# M212X.net
KiCad netlist of a schematic drawn in EAGLE
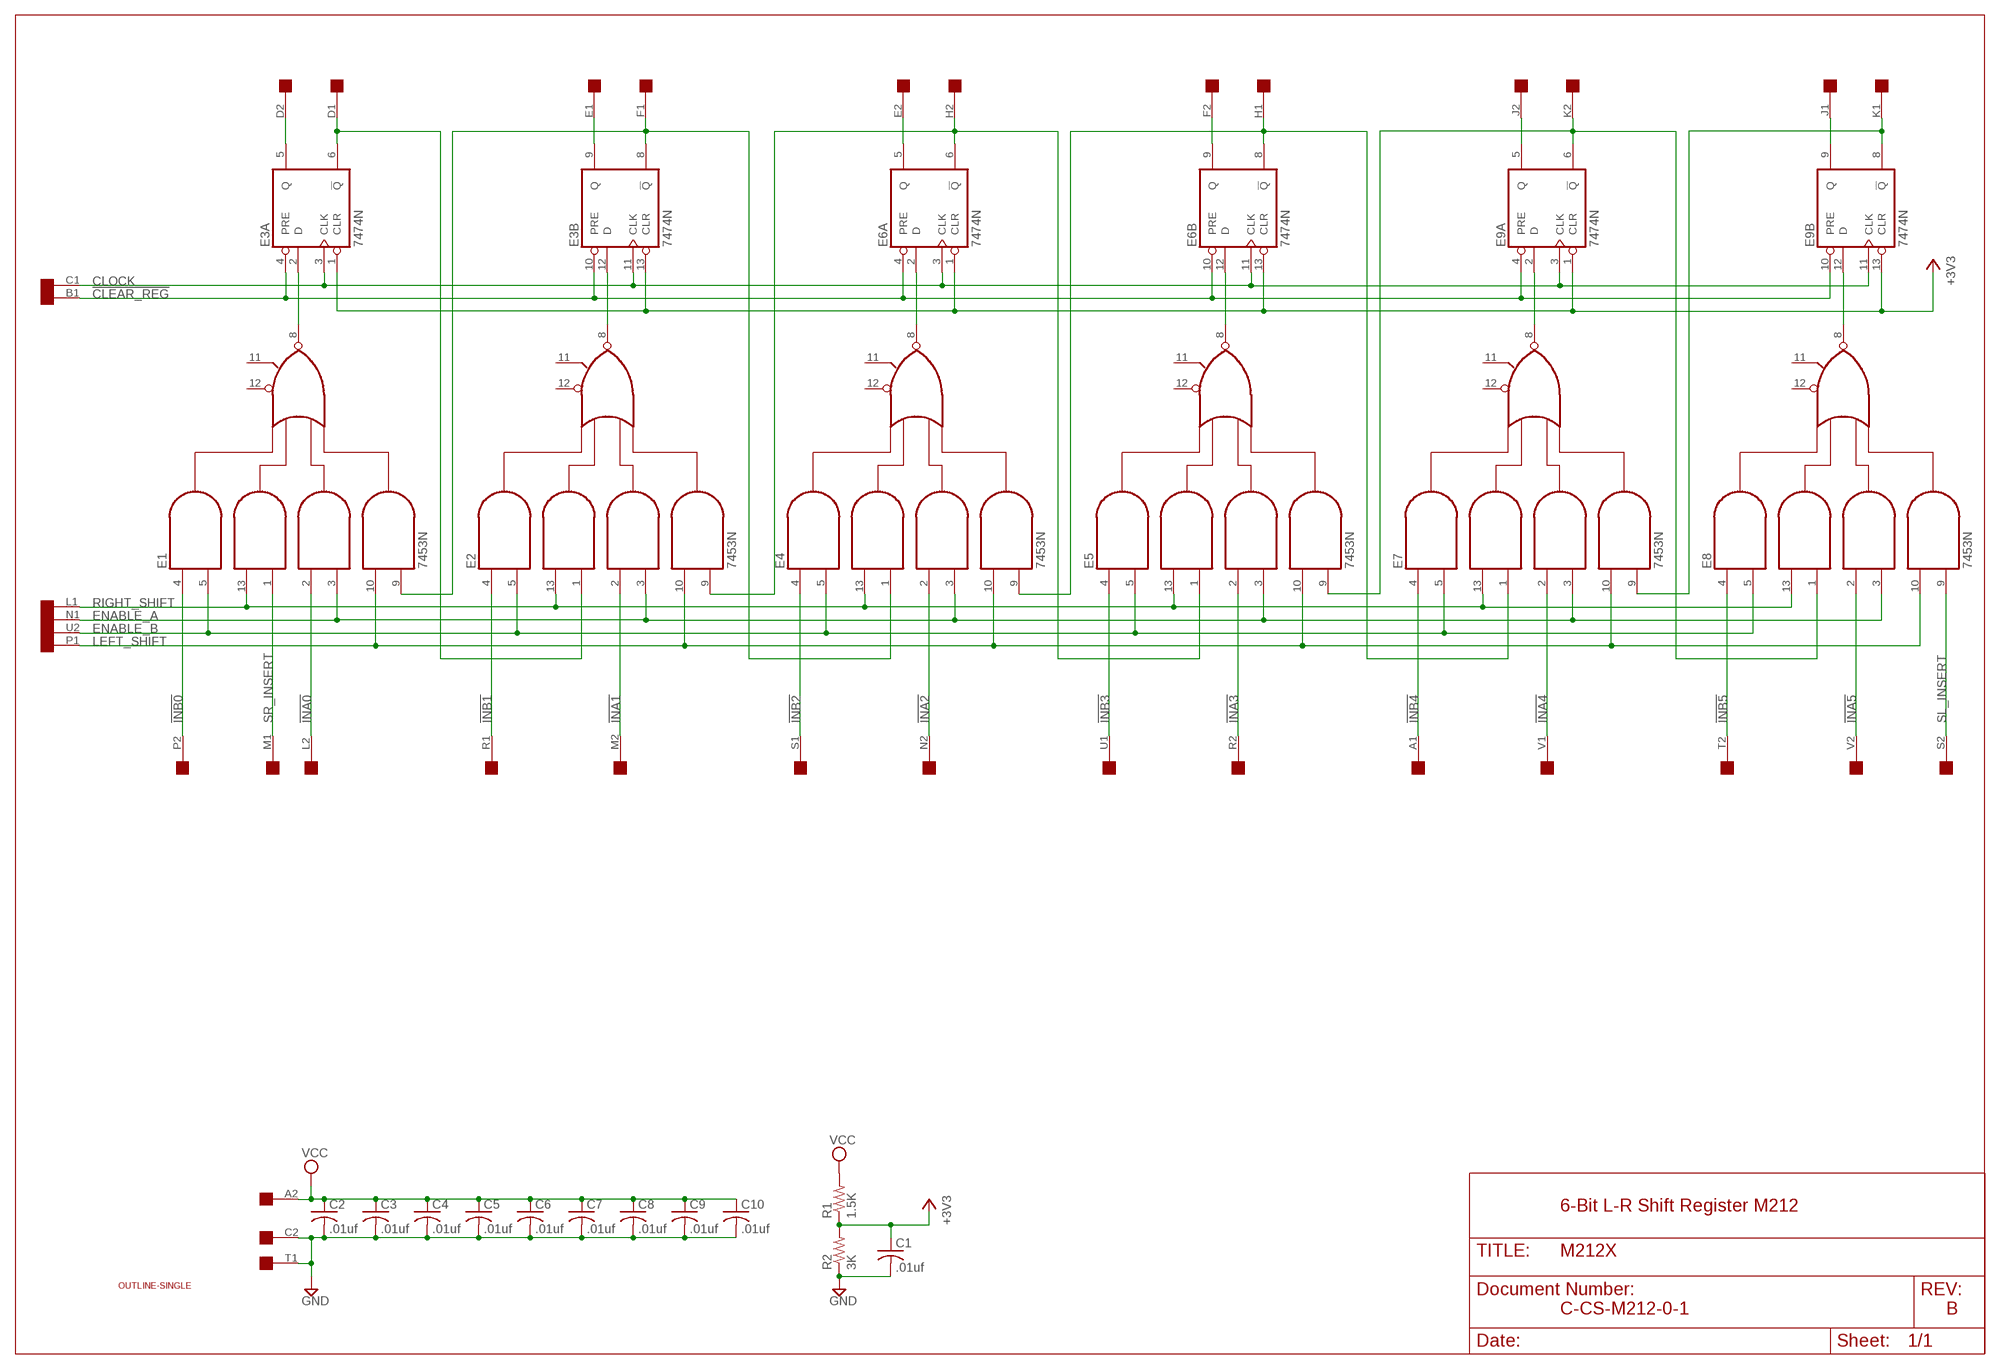
[diagram p0: schematic, sheet 1]

(export (version "E")
  (design (tool "Eeschema 10.0.6"))
  (components
    (comp (ref "C1")
      (value ".01uf")
      (footprint "eagle-import:C050-025X075")
      (libsource (lib "eagle-import") (part "C-US050-025X075"))
    )
    (comp (ref "C2")
      (value ".01uf")
      (footprint "eagle-import:C075-032X103")
      (libsource (lib "eagle-import") (part "C-US075-032X103"))
    )
    (comp (ref "C3")
      (value ".01uf")
      (footprint "eagle-import:C075-032X103")
      (libsource (lib "eagle-import") (part "C-US075-032X103"))
    )
    (comp (ref "C4")
      (value ".01uf")
      (footprint "eagle-import:C075-032X103")
      (libsource (lib "eagle-import") (part "C-US075-032X103"))
    )
    (comp (ref "C5")
      (value ".01uf")
      (footprint "eagle-import:C075-032X103")
      (libsource (lib "eagle-import") (part "C-US075-032X103"))
    )
    (comp (ref "C6")
      (value ".01uf")
      (footprint "eagle-import:C075-032X103")
      (libsource (lib "eagle-import") (part "C-US075-032X103"))
    )
    (comp (ref "C7")
      (value ".01uf")
      (footprint "eagle-import:C075-032X103")
      (libsource (lib "eagle-import") (part "C-US075-032X103"))
    )
    (comp (ref "C8")
      (value ".01uf")
      (footprint "eagle-import:C075-032X103")
      (libsource (lib "eagle-import") (part "C-US075-032X103"))
    )
    (comp (ref "C9")
      (value ".01uf")
      (footprint "eagle-import:C075-032X103")
      (libsource (lib "eagle-import") (part "C-US075-032X103"))
    )
    (comp (ref "C10")
      (value ".01uf")
      (footprint "eagle-import:C075-032X103")
      (libsource (lib "eagle-import") (part "C-US075-032X103"))
    )
    (comp (ref "E1")
      (value "7453N")
      (footprint "eagle-import:DIL14")
      (libsource (lib "eagle-import") (part "7453N"))
    )
    (comp (ref "E2")
      (value "7453N")
      (footprint "eagle-import:DIL14")
      (libsource (lib "eagle-import") (part "7453N"))
    )
    (comp (ref "E3")
      (value "7474N")
      (footprint "eagle-import:DIL14")
      (libsource (lib "eagle-import") (part "7474NS"))
    )
    (comp (ref "E4")
      (value "7453N")
      (footprint "eagle-import:DIL14")
      (libsource (lib "eagle-import") (part "7453N"))
    )
    (comp (ref "E5")
      (value "7453N")
      (footprint "eagle-import:DIL14")
      (libsource (lib "eagle-import") (part "7453N"))
    )
    (comp (ref "E6")
      (value "7474N")
      (footprint "eagle-import:DIL14")
      (libsource (lib "eagle-import") (part "7474NS"))
    )
    (comp (ref "E7")
      (value "7453N")
      (footprint "eagle-import:DIL14")
      (libsource (lib "eagle-import") (part "7453N"))
    )
    (comp (ref "E8")
      (value "7453N")
      (footprint "eagle-import:DIL14")
      (libsource (lib "eagle-import") (part "7453N"))
    )
    (comp (ref "E9")
      (value "7474N")
      (footprint "eagle-import:DIL14")
      (libsource (lib "eagle-import") (part "7474NS"))
    )
    (comp (ref "EDGE1")
      (value "EDGE-2CONNECTOR")
      (footprint "eagle-import:EDGE-CON2")
      (libsource (lib "eagle-import") (part "EDGE-2CONNECTOR"))
    )
    (comp (ref "R1")
      (value "1.5K")
      (footprint "eagle-import:0207_10")
      (libsource (lib "eagle-import") (part "R-US_0207/10"))
    )
    (comp (ref "R2")
      (value "3K")
      (footprint "eagle-import:0207_10")
      (libsource (lib "eagle-import") (part "R-US_0207/10"))
    )
    (comp (ref "U$1")
      (value "OUTLINE-SINGLE")
      (footprint "eagle-import:SINGLE")
      (libsource (lib "eagle-import") (part "OUTLINE-SINGLE"))
    )
  )
  (nets
    (net (code "1") (name "+3V3") (class "Default")
      (node (ref "C1") (pin "1") (pinfunction "1_1") (pintype "passive"))
      (node (ref "E3") (pin "1") (pinfunction "CLR_1") (pintype "input"))
      (node (ref "E3") (pin "13") (pinfunction "CLR_13") (pintype "input"))
      (node (ref "E6") (pin "1") (pinfunction "CLR_1") (pintype "input"))
      (node (ref "E6") (pin "13") (pinfunction "CLR_13") (pintype "input"))
      (node (ref "E9") (pin "1") (pinfunction "CLR_1") (pintype "input"))
      (node (ref "E9") (pin "13") (pinfunction "CLR_13") (pintype "input"))
      (node (ref "R1") (pin "1") (pinfunction "1_1") (pintype "passive"))
      (node (ref "R2") (pin "2") (pinfunction "2_2") (pintype "passive"))
    )
    (net (code "2") (name "/CLOCK") (class "Default")
      (node (ref "E3") (pin "11") (pinfunction "CLK_11") (pintype "input"))
      (node (ref "E3") (pin "3") (pinfunction "CLK_3") (pintype "input"))
      (node (ref "E6") (pin "11") (pinfunction "CLK_11") (pintype "input"))
      (node (ref "E6") (pin "3") (pinfunction "CLK_3") (pintype "input"))
      (node (ref "E9") (pin "11") (pinfunction "CLK_11") (pintype "input"))
      (node (ref "E9") (pin "3") (pinfunction "CLK_3") (pintype "input"))
      (node (ref "EDGE1") (pin "C1") (pinfunction "1_C1") (pintype "bidirectional"))
    )
    (net (code "3") (name "/ENABLE_A") (class "Default")
      (node (ref "E1") (pin "3") (pinfunction "I6_3") (pintype "input"))
      (node (ref "E2") (pin "3") (pinfunction "I6_3") (pintype "input"))
      (node (ref "E4") (pin "3") (pinfunction "I6_3") (pintype "input"))
      (node (ref "E5") (pin "3") (pinfunction "I6_3") (pintype "input"))
      (node (ref "E7") (pin "3") (pinfunction "I6_3") (pintype "input"))
      (node (ref "E8") (pin "3") (pinfunction "I6_3") (pintype "input"))
      (node (ref "EDGE1") (pin "N1") (pinfunction "1_N1") (pintype "bidirectional"))
    )
    (net (code "4") (name "/ENABLE_B") (class "Default")
      (node (ref "E1") (pin "5") (pinfunction "I2_5") (pintype "input"))
      (node (ref "E2") (pin "5") (pinfunction "I2_5") (pintype "input"))
      (node (ref "E4") (pin "5") (pinfunction "I2_5") (pintype "input"))
      (node (ref "E5") (pin "5") (pinfunction "I2_5") (pintype "input"))
      (node (ref "E7") (pin "5") (pinfunction "I2_5") (pintype "input"))
      (node (ref "E8") (pin "5") (pinfunction "I2_5") (pintype "input"))
      (node (ref "EDGE1") (pin "U2") (pinfunction "1_U2") (pintype "bidirectional"))
    )
    (net (code "5") (name "/LEFT_SHIFT") (class "Default")
      (node (ref "E1") (pin "10") (pinfunction "I7_10") (pintype "input"))
      (node (ref "E2") (pin "10") (pinfunction "I7_10") (pintype "input"))
      (node (ref "E4") (pin "10") (pinfunction "I7_10") (pintype "input"))
      (node (ref "E5") (pin "10") (pinfunction "I7_10") (pintype "input"))
      (node (ref "E7") (pin "10") (pinfunction "I7_10") (pintype "input"))
      (node (ref "E8") (pin "10") (pinfunction "I7_10") (pintype "input"))
      (node (ref "EDGE1") (pin "P1") (pinfunction "1_P1") (pintype "bidirectional"))
    )
    (net (code "6") (name "/RIGHT_SHIFT") (class "Default")
      (node (ref "E1") (pin "13") (pinfunction "I3_13") (pintype "input"))
      (node (ref "E2") (pin "13") (pinfunction "I3_13") (pintype "input"))
      (node (ref "E4") (pin "13") (pinfunction "I3_13") (pintype "input"))
      (node (ref "E5") (pin "13") (pinfunction "I3_13") (pintype "input"))
      (node (ref "E7") (pin "13") (pinfunction "I3_13") (pintype "input"))
      (node (ref "E8") (pin "13") (pinfunction "I3_13") (pintype "input"))
      (node (ref "EDGE1") (pin "L1") (pinfunction "1_L1") (pintype "bidirectional"))
    )
    (net (code "7") (name "/SL_INSERT") (class "Default")
      (node (ref "E8") (pin "9") (pinfunction "I8_9") (pintype "input"))
      (node (ref "EDGE1") (pin "S2") (pinfunction "1_S2") (pintype "bidirectional"))
    )
    (net (code "8") (name "/SR_INSERT") (class "Default")
      (node (ref "E1") (pin "1") (pinfunction "I4_1") (pintype "input"))
      (node (ref "EDGE1") (pin "M1") (pinfunction "1_M1") (pintype "bidirectional"))
    )
    (net (code "9") (name "/~{CLEAR_REG}") (class "Default")
      (node (ref "E3") (pin "10") (pinfunction "PRE_10") (pintype "input"))
      (node (ref "E3") (pin "4") (pinfunction "PRE_4") (pintype "input"))
      (node (ref "E6") (pin "10") (pinfunction "PRE_10") (pintype "input"))
      (node (ref "E6") (pin "4") (pinfunction "PRE_4") (pintype "input"))
      (node (ref "E9") (pin "10") (pinfunction "PRE_10") (pintype "input"))
      (node (ref "E9") (pin "4") (pinfunction "PRE_4") (pintype "input"))
      (node (ref "EDGE1") (pin "B1") (pinfunction "1_B1") (pintype "bidirectional"))
    )
    (net (code "10") (name "/~{INA0}") (class "Default")
      (node (ref "E1") (pin "2") (pinfunction "I5_2") (pintype "input"))
      (node (ref "EDGE1") (pin "L2") (pinfunction "1_L2") (pintype "bidirectional"))
    )
    (net (code "11") (name "/~{INA1}") (class "Default")
      (node (ref "E2") (pin "2") (pinfunction "I5_2") (pintype "input"))
      (node (ref "EDGE1") (pin "M2") (pinfunction "1_M2") (pintype "bidirectional"))
    )
    (net (code "12") (name "/~{INA2}") (class "Default")
      (node (ref "E4") (pin "2") (pinfunction "I5_2") (pintype "input"))
      (node (ref "EDGE1") (pin "N2") (pinfunction "1_N2") (pintype "bidirectional"))
    )
    (net (code "13") (name "/~{INA3}") (class "Default")
      (node (ref "E5") (pin "2") (pinfunction "I5_2") (pintype "input"))
      (node (ref "EDGE1") (pin "R2") (pinfunction "1_R2") (pintype "bidirectional"))
    )
    (net (code "14") (name "/~{INA4}") (class "Default")
      (node (ref "E7") (pin "2") (pinfunction "I5_2") (pintype "input"))
      (node (ref "EDGE1") (pin "V1") (pinfunction "1_V1") (pintype "bidirectional"))
    )
    (net (code "15") (name "/~{INA5}") (class "Default")
      (node (ref "E8") (pin "2") (pinfunction "I5_2") (pintype "input"))
      (node (ref "EDGE1") (pin "V2") (pinfunction "1_V2") (pintype "bidirectional"))
    )
    (net (code "16") (name "/~{INB0}") (class "Default")
      (node (ref "E1") (pin "4") (pinfunction "I1_4") (pintype "input"))
      (node (ref "EDGE1") (pin "P2") (pinfunction "1_P2") (pintype "bidirectional"))
    )
    (net (code "17") (name "/~{INB1}") (class "Default")
      (node (ref "E2") (pin "4") (pinfunction "I1_4") (pintype "input"))
      (node (ref "EDGE1") (pin "R1") (pinfunction "1_R1") (pintype "bidirectional"))
    )
    (net (code "18") (name "/~{INB2}") (class "Default")
      (node (ref "E4") (pin "4") (pinfunction "I1_4") (pintype "input"))
      (node (ref "EDGE1") (pin "S1") (pinfunction "1_S1") (pintype "bidirectional"))
    )
    (net (code "19") (name "/~{INB3}") (class "Default")
      (node (ref "E5") (pin "4") (pinfunction "I1_4") (pintype "input"))
      (node (ref "EDGE1") (pin "U1") (pinfunction "1_U1") (pintype "bidirectional"))
    )
    (net (code "20") (name "/~{INB4}") (class "Default")
      (node (ref "E7") (pin "4") (pinfunction "I1_4") (pintype "input"))
      (node (ref "EDGE1") (pin "A1") (pinfunction "1_A1") (pintype "bidirectional"))
    )
    (net (code "21") (name "/~{INB5}") (class "Default")
      (node (ref "E8") (pin "4") (pinfunction "I1_4") (pintype "input"))
      (node (ref "EDGE1") (pin "T2") (pinfunction "1_T2") (pintype "bidirectional"))
    )
    (net (code "22") (name "GND") (class "Default")
      (node (ref "C1") (pin "2") (pinfunction "2_2") (pintype "passive"))
      (node (ref "C10") (pin "2") (pinfunction "2_2") (pintype "passive"))
      (node (ref "C2") (pin "2") (pinfunction "2_2") (pintype "passive"))
      (node (ref "C3") (pin "2") (pinfunction "2_2") (pintype "passive"))
      (node (ref "C4") (pin "2") (pinfunction "2_2") (pintype "passive"))
      (node (ref "C5") (pin "2") (pinfunction "2_2") (pintype "passive"))
      (node (ref "C6") (pin "2") (pinfunction "2_2") (pintype "passive"))
      (node (ref "C7") (pin "2") (pinfunction "2_2") (pintype "passive"))
      (node (ref "C8") (pin "2") (pinfunction "2_2") (pintype "passive"))
      (node (ref "C9") (pin "2") (pinfunction "2_2") (pintype "passive"))
      (node (ref "EDGE1") (pin "C2") (pinfunction "1_C2") (pintype "bidirectional"))
      (node (ref "EDGE1") (pin "T1") (pinfunction "1_T1") (pintype "bidirectional"))
      (node (ref "R2") (pin "1") (pinfunction "1_1") (pintype "passive"))
    )
    (net (code "23") (name "Net-(E1A-I8)") (class "Default")
      (node (ref "E1") (pin "9") (pinfunction "I8_9") (pintype "input"))
      (node (ref "E3") (pin "8") (pinfunction "~{Q}_8") (pintype "output"))
      (node (ref "E4") (pin "1") (pinfunction "I4_1") (pintype "input"))
      (node (ref "EDGE1") (pin "F1") (pinfunction "1_F1") (pintype "bidirectional"))
    )
    (net (code "24") (name "Net-(E1A-O)") (class "Default")
      (node (ref "E1") (pin "8") (pinfunction "O_8") (pintype "output"))
      (node (ref "E3") (pin "2") (pinfunction "D_2") (pintype "input"))
    )
    (net (code "25") (name "Net-(E2A-I4)") (class "Default")
      (node (ref "E2") (pin "1") (pinfunction "I4_1") (pintype "input"))
      (node (ref "E3") (pin "6") (pinfunction "~{Q}_6") (pintype "output"))
      (node (ref "EDGE1") (pin "D1") (pinfunction "1_D1") (pintype "bidirectional"))
    )
    (net (code "26") (name "Net-(E2A-I8)") (class "Default")
      (node (ref "E2") (pin "9") (pinfunction "I8_9") (pintype "input"))
      (node (ref "E5") (pin "1") (pinfunction "I4_1") (pintype "input"))
      (node (ref "E6") (pin "6") (pinfunction "~{Q}_6") (pintype "output"))
      (node (ref "EDGE1") (pin "H2") (pinfunction "1_H2") (pintype "bidirectional"))
    )
    (net (code "27") (name "Net-(E2A-O)") (class "Default")
      (node (ref "E2") (pin "8") (pinfunction "O_8") (pintype "output"))
      (node (ref "E3") (pin "12") (pinfunction "D_12") (pintype "input"))
    )
    (net (code "28") (name "Net-(E3A-Q)") (class "Default")
      (node (ref "E3") (pin "5") (pinfunction "Q_5") (pintype "output"))
      (node (ref "EDGE1") (pin "D2") (pinfunction "1_D2") (pintype "bidirectional"))
    )
    (net (code "29") (name "Net-(E3B-Q)") (class "Default")
      (node (ref "E3") (pin "9") (pinfunction "Q_9") (pintype "output"))
      (node (ref "EDGE1") (pin "E1") (pinfunction "1_E1") (pintype "bidirectional"))
    )
    (net (code "30") (name "Net-(E4A-I8)") (class "Default")
      (node (ref "E4") (pin "9") (pinfunction "I8_9") (pintype "input"))
      (node (ref "E6") (pin "8") (pinfunction "~{Q}_8") (pintype "output"))
      (node (ref "E7") (pin "1") (pinfunction "I4_1") (pintype "input"))
      (node (ref "EDGE1") (pin "H1") (pinfunction "1_H1") (pintype "bidirectional"))
    )
    (net (code "31") (name "Net-(E4A-O)") (class "Default")
      (node (ref "E4") (pin "8") (pinfunction "O_8") (pintype "output"))
      (node (ref "E6") (pin "2") (pinfunction "D_2") (pintype "input"))
    )
    (net (code "32") (name "Net-(E5A-I8)") (class "Default")
      (node (ref "E5") (pin "9") (pinfunction "I8_9") (pintype "input"))
      (node (ref "E8") (pin "1") (pinfunction "I4_1") (pintype "input"))
      (node (ref "E9") (pin "6") (pinfunction "~{Q}_6") (pintype "output"))
      (node (ref "EDGE1") (pin "K2") (pinfunction "1_K2") (pintype "bidirectional"))
    )
    (net (code "33") (name "Net-(E5A-O)") (class "Default")
      (node (ref "E5") (pin "8") (pinfunction "O_8") (pintype "output"))
      (node (ref "E6") (pin "12") (pinfunction "D_12") (pintype "input"))
    )
    (net (code "34") (name "Net-(E6A-Q)") (class "Default")
      (node (ref "E6") (pin "5") (pinfunction "Q_5") (pintype "output"))
      (node (ref "EDGE1") (pin "E2") (pinfunction "1_E2") (pintype "bidirectional"))
    )
    (net (code "35") (name "Net-(E6B-Q)") (class "Default")
      (node (ref "E6") (pin "9") (pinfunction "Q_9") (pintype "output"))
      (node (ref "EDGE1") (pin "F2") (pinfunction "1_F2") (pintype "bidirectional"))
    )
    (net (code "36") (name "Net-(E7A-I8)") (class "Default")
      (node (ref "E7") (pin "9") (pinfunction "I8_9") (pintype "input"))
      (node (ref "E9") (pin "8") (pinfunction "~{Q}_8") (pintype "output"))
      (node (ref "EDGE1") (pin "K1") (pinfunction "1_K1") (pintype "bidirectional"))
    )
    (net (code "37") (name "Net-(E7A-O)") (class "Default")
      (node (ref "E7") (pin "8") (pinfunction "O_8") (pintype "output"))
      (node (ref "E9") (pin "2") (pinfunction "D_2") (pintype "input"))
    )
    (net (code "38") (name "Net-(E8A-O)") (class "Default")
      (node (ref "E8") (pin "8") (pinfunction "O_8") (pintype "output"))
      (node (ref "E9") (pin "12") (pinfunction "D_12") (pintype "input"))
    )
    (net (code "39") (name "Net-(E9A-Q)") (class "Default")
      (node (ref "E9") (pin "5") (pinfunction "Q_5") (pintype "output"))
      (node (ref "EDGE1") (pin "J2") (pinfunction "1_J2") (pintype "bidirectional"))
    )
    (net (code "40") (name "Net-(E9B-Q)") (class "Default")
      (node (ref "E9") (pin "9") (pinfunction "Q_9") (pintype "output"))
      (node (ref "EDGE1") (pin "J1") (pinfunction "1_J1") (pintype "bidirectional"))
    )
    (net (code "41") (name "VCC") (class "Default")
      (node (ref "C10") (pin "1") (pinfunction "1_1") (pintype "passive"))
      (node (ref "C2") (pin "1") (pinfunction "1_1") (pintype "passive"))
      (node (ref "C3") (pin "1") (pinfunction "1_1") (pintype "passive"))
      (node (ref "C4") (pin "1") (pinfunction "1_1") (pintype "passive"))
      (node (ref "C5") (pin "1") (pinfunction "1_1") (pintype "passive"))
      (node (ref "C6") (pin "1") (pinfunction "1_1") (pintype "passive"))
      (node (ref "C7") (pin "1") (pinfunction "1_1") (pintype "passive"))
      (node (ref "C8") (pin "1") (pinfunction "1_1") (pintype "passive"))
      (node (ref "C9") (pin "1") (pinfunction "1_1") (pintype "passive"))
      (node (ref "EDGE1") (pin "A2") (pinfunction "1_A2") (pintype "bidirectional"))
      (node (ref "R1") (pin "2") (pinfunction "2_2") (pintype "passive"))
    )
    (net (code "42") (name "unconnected-(E1A-I9-Pad12)") (class "Default")
      (node (ref "E1") (pin "12") (pinfunction "I9_12") (pintype "passive"))
    )
    (net (code "43") (name "unconnected-(E1A-I10-Pad11)") (class "Default")
      (node (ref "E1") (pin "11") (pinfunction "I10_11") (pintype "passive"))
    )
    (net (code "44") (name "unconnected-(E2A-I9-Pad12)") (class "Default")
      (node (ref "E2") (pin "12") (pinfunction "I9_12") (pintype "passive"))
    )
    (net (code "45") (name "unconnected-(E2A-I10-Pad11)") (class "Default")
      (node (ref "E2") (pin "11") (pinfunction "I10_11") (pintype "passive"))
    )
    (net (code "46") (name "unconnected-(E4A-I9-Pad12)") (class "Default")
      (node (ref "E4") (pin "12") (pinfunction "I9_12") (pintype "passive"))
    )
    (net (code "47") (name "unconnected-(E4A-I10-Pad11)") (class "Default")
      (node (ref "E4") (pin "11") (pinfunction "I10_11") (pintype "passive"))
    )
    (net (code "48") (name "unconnected-(E5A-I9-Pad12)") (class "Default")
      (node (ref "E5") (pin "12") (pinfunction "I9_12") (pintype "passive"))
    )
    (net (code "49") (name "unconnected-(E5A-I10-Pad11)") (class "Default")
      (node (ref "E5") (pin "11") (pinfunction "I10_11") (pintype "passive"))
    )
    (net (code "50") (name "unconnected-(E7A-I9-Pad12)") (class "Default")
      (node (ref "E7") (pin "12") (pinfunction "I9_12") (pintype "passive"))
    )
    (net (code "51") (name "unconnected-(E7A-I10-Pad11)") (class "Default")
      (node (ref "E7") (pin "11") (pinfunction "I10_11") (pintype "passive"))
    )
    (net (code "52") (name "unconnected-(E8A-I9-Pad12)") (class "Default")
      (node (ref "E8") (pin "12") (pinfunction "I9_12") (pintype "passive"))
    )
    (net (code "53") (name "unconnected-(E8A-I10-Pad11)") (class "Default")
      (node (ref "E8") (pin "11") (pinfunction "I10_11") (pintype "passive"))
    )
  )
)
